# NG2094_IMU.net
KiCad netlist of a schematic drawn in Altium Designer
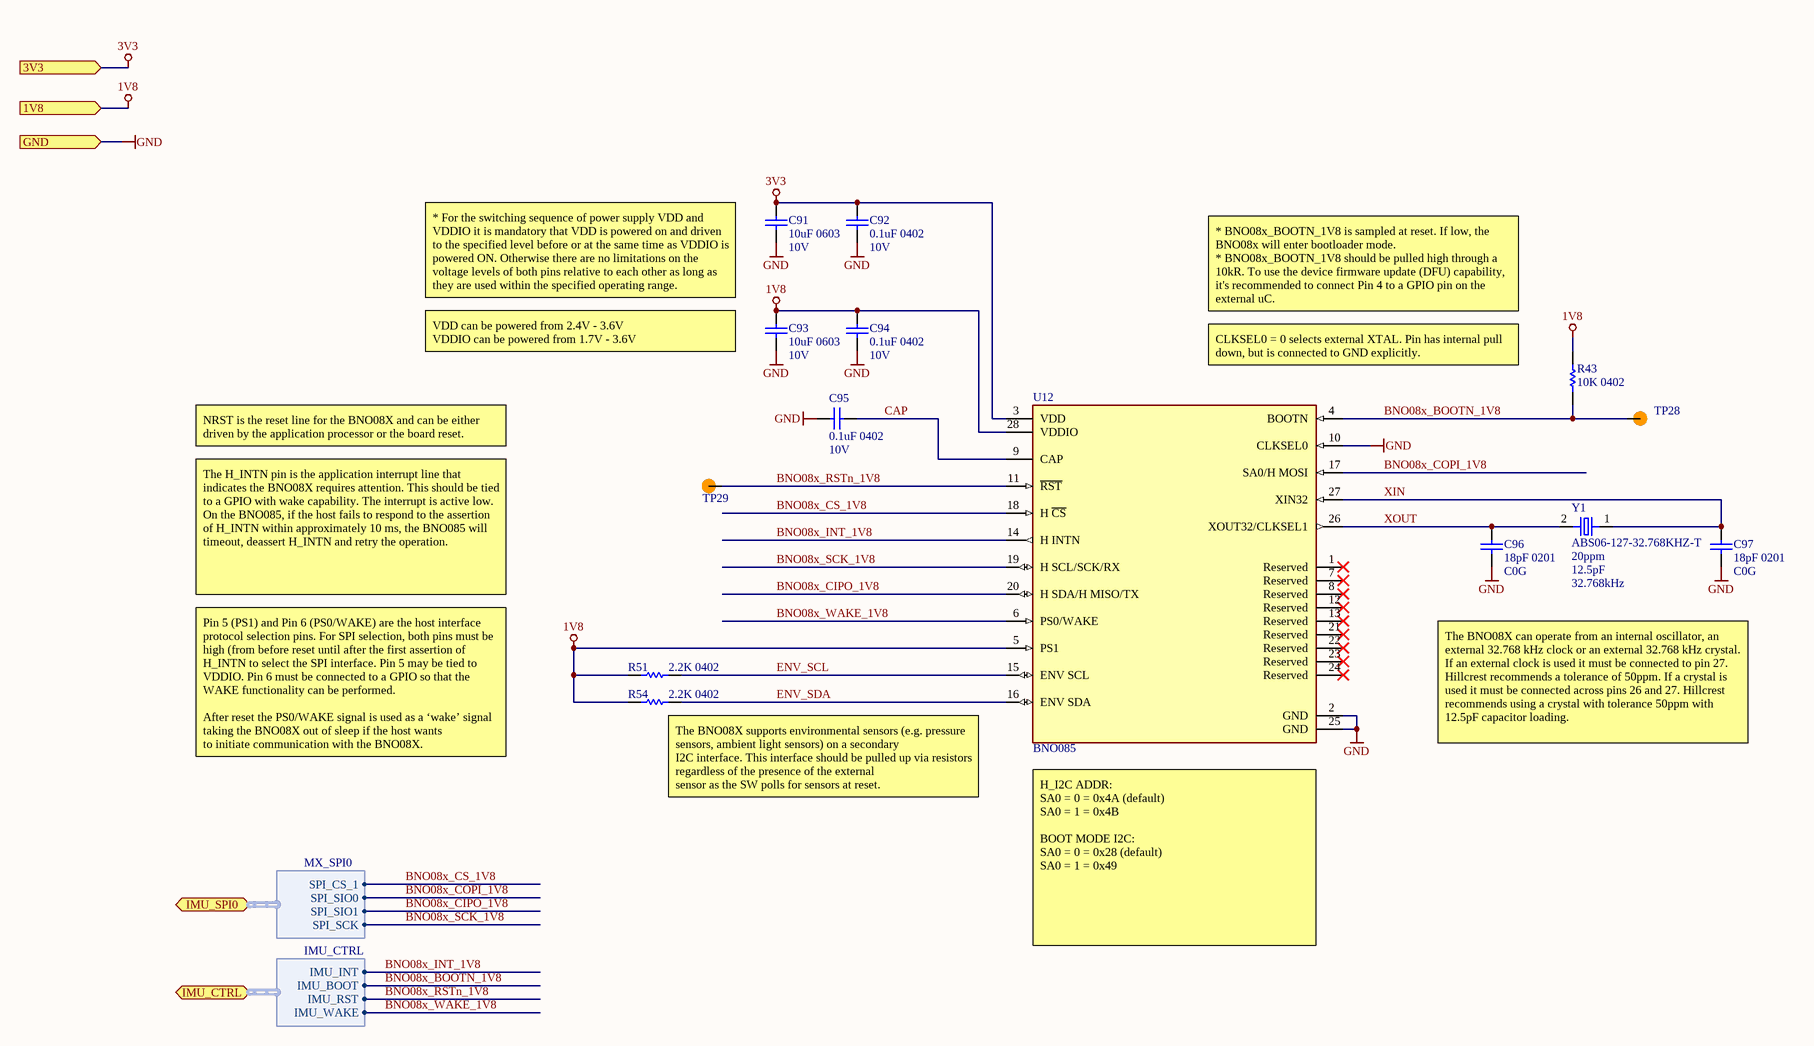
[diagram p0: NG2094_IMU.SchDoc]

(export (version "E")
  (design (tool "Eeschema 10.0.6"))
  (components
    (comp (ref "C91")
      (value "10uF 0603")
      (footprint "CAP_Altium_Vault_Generic:CAPC0603(1608)100_L")
      (description "CAP CER 10UF 10V X5R 0603 20%")
      (fields (field (name "TOLERANCE") "20%") (field (name "VOLTAGE RATING") "10V"))
      (libsource (lib "LuxonisMaster") (part "GRM188R61A106ME69D"))
    )
    (comp (ref "C92")
      (value "0.1uF 0402")
      (footprint "CAP_Altium_Vault_Generic:CAPC0402(1005)70_L")
      (description "CAP CER 0.1UF 10V X7R 0402 5%")
      (fields (field (name "TOLERANCE") "5%") (field (name "VOLTAGE RATING") "10V"))
      (libsource (lib "LuxonisMaster") (part "GRM155R71A104JA01D"))
    )
    (comp (ref "C93")
      (value "10uF 0603")
      (footprint "CAP_Altium_Vault_Generic:CAPC0603(1608)100_L")
      (description "CAP CER 10UF 10V X5R 0603 20%")
      (fields (field (name "TOLERANCE") "20%") (field (name "VOLTAGE RATING") "10V"))
      (libsource (lib "LuxonisMaster") (part "GRM188R61A106ME69D"))
    )
    (comp (ref "C94")
      (value "0.1uF 0402")
      (footprint "CAP_Altium_Vault_Generic:CAPC0402(1005)70_L")
      (description "CAP CER 0.1UF 10V X7R 0402 5%")
      (fields (field (name "TOLERANCE") "5%") (field (name "VOLTAGE RATING") "10V"))
      (libsource (lib "LuxonisMaster") (part "GRM155R71A104JA01D"))
    )
    (comp (ref "C95")
      (value "0.1uF 0402")
      (footprint "CAP_Altium_Vault_Generic:CAPC0402(1005)70_L")
      (description "CAP CER 0.1UF 10V X7R 0402 5%")
      (fields (field (name "TOLERANCE") "5%") (field (name "VOLTAGE RATING") "10V"))
      (libsource (lib "LuxonisMaster") (part "GRM155R71A104JA01D"))
    )
    (comp (ref "C96")
      (value "18pF 0201")
      (footprint "CAPC0201(0603)33_L")
      (description "Cap Ceramic 18pF 25V C0G 1% Pad SMD 0201 125C T/R")
      (fields (field (name "TOLERANCE") "1%") (field (name "DIELECTRIC") "C0G"))
      (libsource (lib "LuxonisMaster") (part "GRM0335C1E180FA01D"))
    )
    (comp (ref "C97")
      (value "18pF 0201")
      (footprint "CAPC0201(0603)33_L")
      (description "Cap Ceramic 18pF 25V C0G 1% Pad SMD 0201 125C T/R")
      (fields (field (name "TOLERANCE") "1%") (field (name "DIELECTRIC") "C0G"))
      (libsource (lib "LuxonisMaster") (part "GRM0335C1E180FA01D"))
    )
    (comp (ref "R43")
      (value "10K 0402")
      (footprint "RES_Altium_Vault_Generic:RESC0402(1005)_L")
      (fields (field (name "TOLERANCE") "1%"))
      (libsource (lib "LuxonisMaster") (part "RC0402FR-1310KL"))
    )
    (comp (ref "R51")
      (value "2.2K 0402")
      (footprint "RES_Altium_Vault_Generic:RESC0402(1005)_L")
      (description "RES SMD 2.2K OHM 1% 1/16W 0402")
      (fields (field (name "TOLERANCE") "1%"))
      (libsource (lib "LuxonisMaster") (part "RC0402FR-072K2L"))
    )
    (comp (ref "R54")
      (value "2.2K 0402")
      (footprint "RES_Altium_Vault_Generic:RESC0402(1005)_L")
      (description "RES SMD 2.2K OHM 1% 1/16W 0402")
      (fields (field (name "TOLERANCE") "1%"))
      (libsource (lib "LuxonisMaster") (part "RC0402FR-072K2L"))
    )
    (comp (ref "TP28")
      (value "TP100_200_NS")
      (footprint "LuxonisMaster:TP100_200_NS")
      (libsource (lib "LuxonisMaster") (part "TEST_POINT"))
    )
    (comp (ref "TP29")
      (value "TP100_200_NS")
      (footprint "LuxonisMaster:TP100_200_NS")
      (libsource (lib "LuxonisMaster") (part "TEST_POINT"))
    )
    (comp (ref "U12")
      (value "BNO085")
      (footprint "BNO085")
      (description "IMU ACCEL/GYRO/MAG I2C 32BIT")
      (libsource (lib "LuxonisMaster") (part "BNO085"))
    )
    (comp (ref "Y1")
      (value "ABS06-127-32.768KHZ-T")
      (footprint "ABS06-127-32.768KHZ-T")
      (description "CRYSTAL 32.768kHz ±20ppm Crystal 12.5pF 90 kOhms 2-SMD, No Lead")
      (fields
        (field (name "FREQUENCY TOLERANCE") "20ppm")
        (field (name "LOAD CAPACITANCE") "12.5pF")
        (field (name "FREQUENCY") "32.768kHz")
      )
      (libsource (lib "LuxonisMaster") (part "ABS06-127-32.768KHZ-T"))
    )
  )
  (nets
    (net (code "3") (name "/BNO08x_BOOTN_1V8") (class "Default")
      (node (ref "R43") (pin "1") (pinfunction "1_1") (pintype "passive"))
      (node (ref "TP28") (pin "1") (pintype "passive"))
      (node (ref "U12") (pin "4") (pinfunction "BOOTN_4") (pintype "input"))
    )
    (net (code "4") (name "/BNO08x_CIPO_1V8") (class "Default")
      (node (ref "U12") (pin "20") (pinfunction "H_SDA/H_MISO/TX_20") (pintype "bidirectional"))
    )
    (net (code "5") (name "/BNO08x_COPI_1V8") (class "Default")
      (node (ref "U12") (pin "17") (pinfunction "SA0/H_MOSI_17") (pintype "input"))
    )
    (net (code "6") (name "/BNO08x_CS_1V8") (class "Default")
      (node (ref "U12") (pin "18") (pinfunction "H_~{CS}_18") (pintype "input"))
    )
    (net (code "7") (name "/BNO08x_INT_1V8") (class "Default")
      (node (ref "U12") (pin "14") (pinfunction "H_INTN_14") (pintype "output"))
    )
    (net (code "8") (name "/BNO08x_RSTn_1V8") (class "Default")
      (node (ref "TP29") (pin "1") (pintype "passive"))
      (node (ref "U12") (pin "11") (pinfunction "~{RST}_11") (pintype "input"))
    )
    (net (code "9") (name "/BNO08x_SCK_1V8") (class "Default")
      (node (ref "U12") (pin "19") (pinfunction "H_SCL/SCK/RX_19") (pintype "bidirectional"))
    )
    (net (code "10") (name "/BNO08x_WAKE_1V8") (class "Default")
      (node (ref "U12") (pin "6") (pinfunction "PS0/WAKE_6") (pintype "input"))
    )
    (net (code "11") (name "/CAP") (class "Default")
      (node (ref "C95") (pin "1") (pinfunction "1_1") (pintype "passive"))
      (node (ref "U12") (pin "9") (pinfunction "CAP_9") (pintype "passive"))
    )
    (net (code "12") (name "/ENV_SCL") (class "Default")
      (node (ref "R51") (pin "2") (pinfunction "2_2") (pintype "passive"))
      (node (ref "U12") (pin "15") (pinfunction "ENV_SCL_15") (pintype "bidirectional"))
    )
    (net (code "13") (name "/ENV_SDA") (class "Default")
      (node (ref "R54") (pin "2") (pinfunction "2_2") (pintype "passive"))
      (node (ref "U12") (pin "16") (pinfunction "ENV_SDA_16") (pintype "bidirectional"))
    )
    (net (code "14") (name "/XIN") (class "Default")
      (node (ref "C97") (pin "2") (pinfunction "2_2") (pintype "passive"))
      (node (ref "U12") (pin "27") (pinfunction "XIN32_27") (pintype "input"))
      (node (ref "Y1") (pin "1") (pinfunction "1_1") (pintype "passive"))
    )
    (net (code "15") (name "/XOUT") (class "Default")
      (node (ref "C96") (pin "2") (pinfunction "2_2") (pintype "passive"))
      (node (ref "U12") (pin "26") (pinfunction "XOUT32/CLKSEL1_26") (pintype "output"))
      (node (ref "Y1") (pin "2") (pinfunction "2_2") (pintype "passive"))
    )
    (net (code "18") (name "1V8") (class "Default")
      (node (ref "C93") (pin "2") (pinfunction "2_2") (pintype "passive"))
      (node (ref "C94") (pin "2") (pinfunction "2_2") (pintype "passive"))
      (node (ref "R43") (pin "2") (pinfunction "2_2") (pintype "passive"))
      (node (ref "R51") (pin "1") (pinfunction "1_1") (pintype "passive"))
      (node (ref "R54") (pin "1") (pinfunction "1_1") (pintype "passive"))
      (node (ref "U12") (pin "28") (pinfunction "VDDIO_28") (pintype "power_in"))
      (node (ref "U12") (pin "5") (pinfunction "PS1_5") (pintype "input"))
    )
    (net (code "19") (name "3V3") (class "Default")
      (node (ref "C91") (pin "2") (pinfunction "2_2") (pintype "passive"))
      (node (ref "C92") (pin "2") (pinfunction "2_2") (pintype "passive"))
      (node (ref "U12") (pin "3") (pinfunction "VDD_3") (pintype "power_in"))
    )
    (net (code "20") (name "GND") (class "Default")
      (node (ref "C91") (pin "1") (pinfunction "1_1") (pintype "passive"))
      (node (ref "C92") (pin "1") (pinfunction "1_1") (pintype "passive"))
      (node (ref "C93") (pin "1") (pinfunction "1_1") (pintype "passive"))
      (node (ref "C94") (pin "1") (pinfunction "1_1") (pintype "passive"))
      (node (ref "C95") (pin "2") (pinfunction "2_2") (pintype "passive"))
      (node (ref "C96") (pin "1") (pinfunction "1_1") (pintype "passive"))
      (node (ref "C97") (pin "1") (pinfunction "1_1") (pintype "passive"))
      (node (ref "U12") (pin "10") (pinfunction "CLKSEL0_10") (pintype "input"))
      (node (ref "U12") (pin "2") (pinfunction "GND_2") (pintype "power_in"))
      (node (ref "U12") (pin "25") (pinfunction "GND_25") (pintype "power_in"))
    )
    (net (code "21") (name "unconnected-(U12-Reserved-Pad1)") (class "Default")
      (node (ref "U12") (pin "1") (pinfunction "Reserved_1") (pintype "passive+no_connect"))
    )
    (net (code "22") (name "unconnected-(U12-Reserved-Pad7)") (class "Default")
      (node (ref "U12") (pin "7") (pinfunction "Reserved_7") (pintype "passive+no_connect"))
    )
    (net (code "23") (name "unconnected-(U12-Reserved-Pad8)") (class "Default")
      (node (ref "U12") (pin "8") (pinfunction "Reserved_8") (pintype "passive+no_connect"))
    )
    (net (code "24") (name "unconnected-(U12-Reserved-Pad12)") (class "Default")
      (node (ref "U12") (pin "12") (pinfunction "Reserved_12") (pintype "passive+no_connect"))
    )
    (net (code "25") (name "unconnected-(U12-Reserved-Pad13)") (class "Default")
      (node (ref "U12") (pin "13") (pinfunction "Reserved_13") (pintype "passive+no_connect"))
    )
    (net (code "26") (name "unconnected-(U12-Reserved-Pad21)") (class "Default")
      (node (ref "U12") (pin "21") (pinfunction "Reserved_21") (pintype "passive+no_connect"))
    )
    (net (code "27") (name "unconnected-(U12-Reserved-Pad22)") (class "Default")
      (node (ref "U12") (pin "22") (pinfunction "Reserved_22") (pintype "passive+no_connect"))
    )
    (net (code "28") (name "unconnected-(U12-Reserved-Pad23)") (class "Default")
      (node (ref "U12") (pin "23") (pinfunction "Reserved_23") (pintype "passive+no_connect"))
    )
    (net (code "29") (name "unconnected-(U12-Reserved-Pad24)") (class "Default")
      (node (ref "U12") (pin "24") (pinfunction "Reserved_24") (pintype "passive+no_connect"))
    )
  )
)
